# Sheet1.net
KiCad netlist of a schematic drawn in Altium Designer
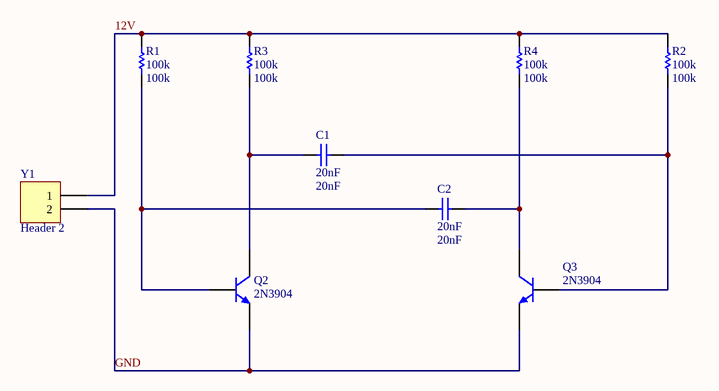
[diagram p0: Sheet1.SchDoc]

(export (version "E")
  (design (tool "Eeschema 10.0.6"))
  (components
    (comp (ref "C1")
      (value "20nF")
      (footprint "RAD-0.3")
      (description "Capacitor")
      (fields (field (name "ALTIUM_VALUE") "20nF") (field (name "PUBLISHER") "Altium Limited"))
      (libsource (lib "Miscellaneous Devices") (part "Cap"))
    )
    (comp (ref "C2")
      (value "20nF")
      (footprint "RAD-0.3")
      (description "Capacitor")
      (fields (field (name "ALTIUM_VALUE") "20nF") (field (name "PUBLISHER") "Altium Limited"))
      (libsource (lib "Miscellaneous Devices") (part "Cap"))
    )
    (comp (ref "Q2")
      (value "2N3904")
      (footprint "TO-92A")
      (description "NPN General Purpose Amplifier")
      (fields (field (name "PUBLISHER") "Altium Limited"))
      (libsource (lib "Miscellaneous Devices") (part "2N3904"))
    )
    (comp (ref "Q3")
      (value "2N3904")
      (footprint "TO-92A")
      (description "NPN General Purpose Amplifier")
      (fields (field (name "PUBLISHER") "Altium Limited"))
      (libsource (lib "Miscellaneous Devices") (part "2N3904"))
    )
    (comp (ref "R1")
      (value "100k")
      (footprint "AXIAL-0.3")
      (description "Resistor")
      (fields (field (name "ALTIUM_VALUE") "100k") (field (name "PUBLISHER") "Altium Limited"))
      (libsource (lib "Miscellaneous Devices") (part "Res1"))
    )
    (comp (ref "R2")
      (value "100k")
      (footprint "AXIAL-0.3")
      (description "Resistor")
      (fields (field (name "ALTIUM_VALUE") "100k") (field (name "PUBLISHER") "Altium Limited"))
      (libsource (lib "Miscellaneous Devices") (part "Res1"))
    )
    (comp (ref "R3")
      (value "100k")
      (footprint "AXIAL-0.3")
      (description "Resistor")
      (fields (field (name "ALTIUM_VALUE") "100k") (field (name "PUBLISHER") "Altium Limited"))
      (libsource (lib "Miscellaneous Devices") (part "Res1"))
    )
    (comp (ref "R4")
      (value "100k")
      (footprint "AXIAL-0.3")
      (description "Resistor")
      (fields (field (name "ALTIUM_VALUE") "100k") (field (name "PUBLISHER") "Altium Limited"))
      (libsource (lib "Miscellaneous Devices") (part "Res1"))
    )
    (comp (ref "Y1")
      (value "Header 2")
      (footprint "HDR1X2")
      (description "Header, 2-Pin")
      (fields (field (name "PUBLISHER") "Altium Limited"))
      (libsource (lib "Miscellaneous Connectors") (part "Header 2"))
    )
  )
  (nets
    (net (code "1") (name "/12V") (class "Default")
      (node (ref "R1") (pin "2") (pinfunction "2_2") (pintype "passive"))
      (node (ref "R2") (pin "2") (pinfunction "2_2") (pintype "passive"))
      (node (ref "R3") (pin "2") (pinfunction "2_2") (pintype "passive"))
      (node (ref "R4") (pin "2") (pinfunction "2_2") (pintype "passive"))
      (node (ref "Y1") (pin "1") (pinfunction "1_1") (pintype "passive"))
    )
    (net (code "2") (name "/GND") (class "Default")
      (node (ref "Q2") (pin "1") (pinfunction "E_1") (pintype "passive"))
      (node (ref "Q3") (pin "1") (pinfunction "E_1") (pintype "passive"))
      (node (ref "Y1") (pin "2") (pinfunction "2_2") (pintype "passive"))
    )
    (net (code "3") (name "Net-(Q2-B)") (class "Default")
      (node (ref "C2") (pin "1") (pinfunction "1_1") (pintype "passive"))
      (node (ref "Q2") (pin "2") (pinfunction "B_2") (pintype "passive"))
      (node (ref "R1") (pin "1") (pinfunction "1_1") (pintype "passive"))
    )
    (net (code "4") (name "Net-(Q2-C)") (class "Default")
      (node (ref "C1") (pin "1") (pinfunction "1_1") (pintype "passive"))
      (node (ref "Q2") (pin "3") (pinfunction "C_3") (pintype "passive"))
      (node (ref "R3") (pin "1") (pinfunction "1_1") (pintype "passive"))
    )
    (net (code "5") (name "Net-(Q3-B)") (class "Default")
      (node (ref "C1") (pin "2") (pinfunction "2_2") (pintype "passive"))
      (node (ref "Q3") (pin "2") (pinfunction "B_2") (pintype "passive"))
      (node (ref "R2") (pin "1") (pinfunction "1_1") (pintype "passive"))
    )
    (net (code "6") (name "Net-(Q3-C)") (class "Default")
      (node (ref "C2") (pin "2") (pinfunction "2_2") (pintype "passive"))
      (node (ref "Q3") (pin "3") (pinfunction "C_3") (pintype "passive"))
      (node (ref "R4") (pin "1") (pinfunction "1_1") (pintype "passive"))
    )
  )
)
